# LPS22HB_pcb_v2.net
KiCad netlist of a schematic drawn in EAGLE
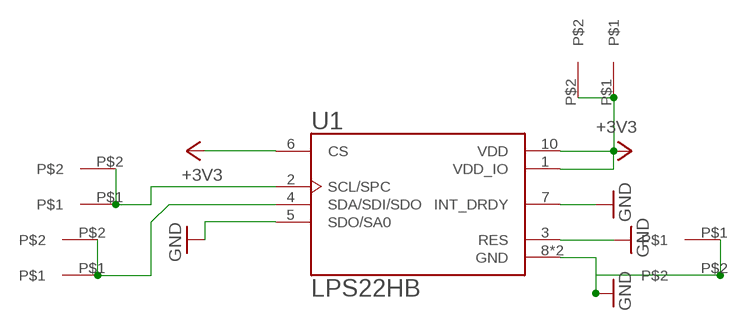
[diagram p0: schematic, sheet 1]

(export (version "E")
  (design (tool "Eeschema 10.0.6"))
  (components
    (comp (ref "U$1")
      (value "WIREPAD_PADWIREPAD_0,6/0,4_PAD")
      (footprint "eagle-import:WIREPAD_0,6_0,4_PAD")
      (libsource (lib "eagle-import") (part "WIREPAD_PADWIREPAD_0,6/0,4_PAD"))
    )
    (comp (ref "U$2")
      (value "WIREPAD_PADWIREPAD_0,6/0,4_PAD")
      (footprint "eagle-import:WIREPAD_0,6_0,4_PAD")
      (libsource (lib "eagle-import") (part "WIREPAD_PADWIREPAD_0,6/0,4_PAD"))
    )
    (comp (ref "U$6")
      (value "WIREPAD_PADWIREPAD_0,6/0,4_PAD")
      (footprint "eagle-import:WIREPAD_0,6_0,4_PAD")
      (libsource (lib "eagle-import") (part "WIREPAD_PADWIREPAD_0,6/0,4_PAD"))
    )
    (comp (ref "U$7")
      (value "WIREPAD_PADWIREPAD_0,6/0,4_PAD")
      (footprint "eagle-import:WIREPAD_0,6_0,4_PAD")
      (libsource (lib "eagle-import") (part "WIREPAD_PADWIREPAD_0,6/0,4_PAD"))
    )
    (comp (ref "U1")
      (value "LPS22HB")
      (footprint "eagle-import:LGA10R50P2X3_200X200X80")
      (fields (field (name "MF") "STMicroelectronics"))
      (libsource (lib "eagle-import") (part "LPS22HB"))
    )
  )
  (nets
    (net (code "1") (name "+3V3") (class "Default")
      (node (ref "U$1") (pin "P$1") (pinfunction "P$1_P$1") (pintype "bidirectional"))
      (node (ref "U$1") (pin "P$2") (pinfunction "P$2_P$2") (pintype "bidirectional"))
      (node (ref "U1") (pin "1") (pinfunction "VDD_IO_1") (pintype "power_in"))
      (node (ref "U1") (pin "10") (pinfunction "VDD_10") (pintype "power_in"))
      (node (ref "U1") (pin "6") (pinfunction "CS_6") (pintype "input"))
    )
    (net (code "2") (name "GND") (class "Default")
      (node (ref "U$2") (pin "P$1") (pinfunction "P$1_P$1") (pintype "bidirectional"))
      (node (ref "U$2") (pin "P$2") (pinfunction "P$2_P$2") (pintype "bidirectional"))
      (node (ref "U1") (pin "3") (pinfunction "RES_3") (pintype "power_in"))
      (node (ref "U1") (pin "5") (pinfunction "SDO/SA0_5") (pintype "bidirectional"))
      (node (ref "U1") (pin "7") (pinfunction "INT_DRDY_7") (pintype "output"))
      (node (ref "U1") (pin "8") (pinfunction "GND_8") (pintype "power_in"))
      (node (ref "U1") (pin "9") (pinfunction "GND_9") (pintype "power_in"))
    )
    (net (code "3") (name "Net-(U1-SCL{slash}SPC)") (class "Default")
      (node (ref "U$6") (pin "P$1") (pinfunction "P$1_P$1") (pintype "bidirectional"))
      (node (ref "U$6") (pin "P$2") (pinfunction "P$2_P$2") (pintype "bidirectional"))
      (node (ref "U1") (pin "2") (pinfunction "SCL/SPC_2") (pintype "input"))
    )
    (net (code "4") (name "Net-(U1-SDA{slash}SDI{slash}SDO)") (class "Default")
      (node (ref "U$7") (pin "P$1") (pinfunction "P$1_P$1") (pintype "bidirectional"))
      (node (ref "U$7") (pin "P$2") (pinfunction "P$2_P$2") (pintype "bidirectional"))
      (node (ref "U1") (pin "4") (pinfunction "SDA/SDI/SDO_4") (pintype "bidirectional"))
    )
  )
)
